# Sheet1.net
KiCad netlist of a schematic drawn in Altium Designer
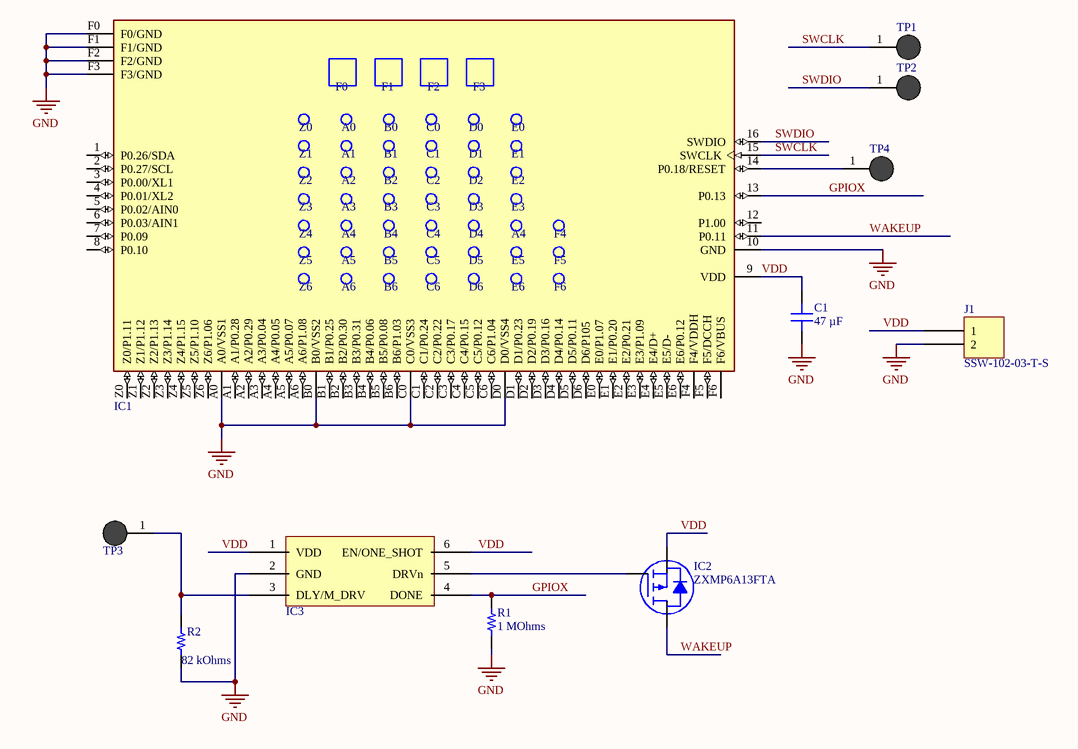
[diagram p0: Sheet1.SchDoc]

(export (version "E")
  (design (tool "Eeschema 10.0.6"))
  (components
    (comp (ref "C1")
      (value "47 µF")
      (footprint "CAP 1206_3216 - 0.8MM")
      (description "CAP CER 47UF 10V X5R 1206")
      (fields
        (field (name "PART NUMBER") "GRM31CR61A476ME15L")
        (field (name "MANUFACTURER") "Murata Electronics")
      )
      (libsource (lib "Celestial Altium Library - altium_library") (part "Capacitor"))
    )
    (comp (ref "IC1")
      (value "BT480F")
      (footprint "BT840F")
      (description "BLE 5 Module: Nordic nRF52840 SoC (Range 930 Meters)")
      (fields
        (field (name "MANUFACTURER") "Fanstel")
        (field (name "MANUFACTURER PART NUMBER") "BT840F")
        (field (name "DESIGNED BY") "Semih AŞÇI")
      )
      (libsource (lib "Integrated_Library1") (part "BT840F"))
    )
    (comp (ref "IC2")
      (value "ZXMP6A13FTA")
      (footprint "DIODES SOT-23-3")
      (description "MOSFET P-CH 60V 0.9A SOT23-3")
      (fields (field (name "MANUFACTURER") "Diodes Incorporated"))
      (libsource (lib "Celestial Altium Library - altium_library") (part "DIODES MOSFET P-CH SOT-23-3"))
    )
    (comp (ref "IC3")
      (value "TPL5111DDCT")
      (footprint "SOT-23-THN-6")
      (fields (field (name "MANUFACTURER") "Texas Instruments") (field (name "DESIGNED BY") "Semih AŞÇI"))
      (libsource (lib "Integrated_Library1") (part "TPL5111"))
    )
    (comp (ref "J1")
      (value "SSW-102-03-T-S")
      (footprint "SAMTEC SSW-102-03-T-S")
      (description "CONN RCPT 2POS 0.1 TIN PCB")
      (fields (field (name "MANUFACTURER") "Samtec Inc."))
      (libsource (lib "Celestial Altium Library - altium_library") (part "2 Pin"))
    )
    (comp (ref "R1")
      (value "1 MOhms")
      (footprint "RES 1206_3216")
      (description "RES SMD 1M OHM 1% 1/4W 1206")
      (fields (field (name "PART NUMBER") "RCA12061M00FKEA") (field (name "MANUFACTURER") "Vishay Dale"))
      (libsource (lib "Celestial Altium Library - altium_library") (part "Resistor"))
    )
    (comp (ref "R2")
      (value "82 kOhms")
      (footprint "RES 1206_3216")
      (description "RES 82K OHM 1% 1/2W 1206")
      (fields
        (field (name "PART NUMBER") "CRGP1206F82K")
        (field (name "MANUFACTURER") "TE Connectivity Passive Product")
      )
      (libsource (lib "Celestial Altium Library - altium_library") (part "Resistor"))
    )
    (comp (ref "TP1")
      (value "TEST PAD")
      (footprint "TEST_PAD")
      (libsource (lib "Integrated_Library1") (part "TEST PAD"))
    )
    (comp (ref "TP2")
      (value "TEST PAD")
      (footprint "TEST_PAD")
      (libsource (lib "Integrated_Library1") (part "TEST PAD"))
    )
    (comp (ref "TP3")
      (value "TEST PAD")
      (footprint "TEST_PAD")
      (libsource (lib "Integrated_Library1") (part "TEST PAD"))
    )
    (comp (ref "TP4")
      (value "TEST PAD")
      (footprint "TEST_PAD")
      (libsource (lib "Integrated_Library1") (part "TEST PAD"))
    )
  )
  (nets
    (net (code "1") (name "/GPIOX") (class "Default")
      (node (ref "IC1") (pin "13") (pinfunction "P0.13_13") (pintype "bidirectional"))
      (node (ref "IC3") (pin "4") (pinfunction "DONE_4") (pintype "passive"))
      (node (ref "R1") (pin "2") (pinfunction "2_2") (pintype "passive"))
    )
    (net (code "2") (name "/SWCLK") (class "Default")
      (node (ref "IC1") (pin "15") (pinfunction "SWCLK_15") (pintype "input"))
      (node (ref "TP1") (pin "1") (pinfunction "1_1") (pintype "passive"))
    )
    (net (code "3") (name "/SWDIO") (class "Default")
      (node (ref "IC1") (pin "16") (pinfunction "SWDIO_16") (pintype "bidirectional"))
      (node (ref "TP2") (pin "1") (pinfunction "1_1") (pintype "passive"))
    )
    (net (code "4") (name "/VDD") (class "Default")
      (node (ref "C1") (pin "2") (pinfunction "2_2") (pintype "passive"))
      (node (ref "IC1") (pin "9") (pinfunction "VDD_9") (pintype "power_in"))
      (node (ref "IC2") (pin "2") (pinfunction "S_2") (pintype "passive"))
      (node (ref "IC3") (pin "1") (pinfunction "VDD_1") (pintype "passive"))
      (node (ref "IC3") (pin "6") (pinfunction "EN/ONE_SHOT_6") (pintype "passive"))
      (node (ref "J1") (pin "1") (pinfunction "1_1") (pintype "passive"))
    )
    (net (code "5") (name "/WAKEUP") (class "Default")
      (node (ref "IC1") (pin "11") (pinfunction "P0.11_11") (pintype "bidirectional"))
      (node (ref "IC2") (pin "3") (pinfunction "D_3") (pintype "passive"))
    )
    (net (code "6") (name "GND") (class "Default")
      (node (ref "C1") (pin "1") (pinfunction "1_1") (pintype "passive"))
      (node (ref "IC1") (pin "10") (pinfunction "GND_10") (pintype "power_in"))
      (node (ref "IC1") (pin "A0") (pinfunction "A0/VSS1_A0") (pintype "power_in"))
      (node (ref "IC1") (pin "B0") (pinfunction "B0/VSS2_B0") (pintype "power_in"))
      (node (ref "IC1") (pin "C0") (pinfunction "C0/VSS3_C0") (pintype "power_in"))
      (node (ref "IC1") (pin "D0") (pinfunction "D0/VSS4_D0") (pintype "power_in"))
      (node (ref "IC1") (pin "F0") (pinfunction "F0/GND_F0") (pintype "power_in"))
      (node (ref "IC1") (pin "F1") (pinfunction "F1/GND_F1") (pintype "power_in"))
      (node (ref "IC1") (pin "F2") (pinfunction "F2/GND_F2") (pintype "power_in"))
      (node (ref "IC1") (pin "F3") (pinfunction "F3/GND_F3") (pintype "power_in"))
      (node (ref "IC3") (pin "2") (pinfunction "GND_2") (pintype "passive"))
      (node (ref "J1") (pin "2") (pinfunction "2_2") (pintype "passive"))
      (node (ref "R1") (pin "1") (pinfunction "1_1") (pintype "passive"))
      (node (ref "R2") (pin "1") (pinfunction "1_1") (pintype "passive"))
    )
    (net (code "7") (name "Net-(IC1-P0.18{slash}RESET)") (class "Default")
      (node (ref "IC1") (pin "14") (pinfunction "P0.18/RESET_14") (pintype "bidirectional"))
      (node (ref "TP4") (pin "1") (pinfunction "1_1") (pintype "passive"))
    )
    (net (code "8") (name "Net-(IC2-G)") (class "Default")
      (node (ref "IC2") (pin "1") (pinfunction "G_1") (pintype "passive"))
      (node (ref "IC3") (pin "5") (pinfunction "DRVn_5") (pintype "passive"))
    )
    (net (code "9") (name "Net-(IC3-DLY{slash}M_DRV)") (class "Default")
      (node (ref "IC3") (pin "3") (pinfunction "DLY/M_DRV_3") (pintype "passive"))
      (node (ref "R2") (pin "2") (pinfunction "2_2") (pintype "passive"))
      (node (ref "TP3") (pin "1") (pinfunction "1_1") (pintype "passive"))
    )
    (net (code "10") (name "unconnected-(IC1-A1{slash}P0.28-PadA1)") (class "Default")
      (node (ref "IC1") (pin "A1") (pinfunction "A1/P0.28_A1") (pintype "bidirectional"))
    )
    (net (code "11") (name "unconnected-(IC1-A2{slash}P0.29-PadA2)") (class "Default")
      (node (ref "IC1") (pin "A2") (pinfunction "A2/P0.29_A2") (pintype "bidirectional"))
    )
    (net (code "12") (name "unconnected-(IC1-A3{slash}P0.04-PadA3)") (class "Default")
      (node (ref "IC1") (pin "A3") (pinfunction "A3/P0.04_A3") (pintype "bidirectional"))
    )
    (net (code "13") (name "unconnected-(IC1-A4{slash}P0.05-PadA4)") (class "Default")
      (node (ref "IC1") (pin "A4") (pinfunction "A4/P0.05_A4") (pintype "bidirectional"))
    )
    (net (code "14") (name "unconnected-(IC1-A5{slash}P0.07-PadA5)") (class "Default")
      (node (ref "IC1") (pin "A5") (pinfunction "A5/P0.07_A5") (pintype "bidirectional"))
    )
    (net (code "15") (name "unconnected-(IC1-A6{slash}P1.08-PadA6)") (class "Default")
      (node (ref "IC1") (pin "A6") (pinfunction "A6/P1.08_A6") (pintype "bidirectional"))
    )
    (net (code "16") (name "unconnected-(IC1-B1{slash}P0.25-PadB1)") (class "Default")
      (node (ref "IC1") (pin "B1") (pinfunction "B1/P0.25_B1") (pintype "bidirectional"))
    )
    (net (code "17") (name "unconnected-(IC1-B2{slash}P0.30-PadB2)") (class "Default")
      (node (ref "IC1") (pin "B2") (pinfunction "B2/P0.30_B2") (pintype "bidirectional"))
    )
    (net (code "18") (name "unconnected-(IC1-B3{slash}P0.31-PadB3)") (class "Default")
      (node (ref "IC1") (pin "B3") (pinfunction "B3/P0.31_B3") (pintype "bidirectional"))
    )
    (net (code "19") (name "unconnected-(IC1-B4{slash}P0.06-PadB4)") (class "Default")
      (node (ref "IC1") (pin "B4") (pinfunction "B4/P0.06_B4") (pintype "bidirectional"))
    )
    (net (code "20") (name "unconnected-(IC1-B5{slash}P0.08-PadB5)") (class "Default")
      (node (ref "IC1") (pin "B5") (pinfunction "B5/P0.08_B5") (pintype "bidirectional"))
    )
    (net (code "21") (name "unconnected-(IC1-B6{slash}P1.03-PadB6)") (class "Default")
      (node (ref "IC1") (pin "B6") (pinfunction "B6/P1.03_B6") (pintype "bidirectional"))
    )
    (net (code "22") (name "unconnected-(IC1-C1{slash}P0.24-PadC1)") (class "Default")
      (node (ref "IC1") (pin "C1") (pinfunction "C1/P0.24_C1") (pintype "bidirectional"))
    )
    (net (code "23") (name "unconnected-(IC1-C2{slash}P0.22-PadC2)") (class "Default")
      (node (ref "IC1") (pin "C2") (pinfunction "C2/P0.22_C2") (pintype "bidirectional"))
    )
    (net (code "24") (name "unconnected-(IC1-C3{slash}P0.17-PadC3)") (class "Default")
      (node (ref "IC1") (pin "C3") (pinfunction "C3/P0.17_C3") (pintype "bidirectional"))
    )
    (net (code "25") (name "unconnected-(IC1-C4{slash}P0.15-PadC4)") (class "Default")
      (node (ref "IC1") (pin "C4") (pinfunction "C4/P0.15_C4") (pintype "bidirectional"))
    )
    (net (code "26") (name "unconnected-(IC1-C5{slash}P0.12-PadC5)") (class "Default")
      (node (ref "IC1") (pin "C5") (pinfunction "C5/P0.12_C5") (pintype "bidirectional"))
    )
    (net (code "27") (name "unconnected-(IC1-C6{slash}P1.04-PadC6)") (class "Default")
      (node (ref "IC1") (pin "C6") (pinfunction "C6/P1.04_C6") (pintype "bidirectional"))
    )
    (net (code "28") (name "unconnected-(IC1-D1{slash}P0.23-PadD1)") (class "Default")
      (node (ref "IC1") (pin "D1") (pinfunction "D1/P0.23_D1") (pintype "bidirectional"))
    )
    (net (code "29") (name "unconnected-(IC1-D2{slash}P0.19-PadD2)") (class "Default")
      (node (ref "IC1") (pin "D2") (pinfunction "D2/P0.19_D2") (pintype "bidirectional"))
    )
    (net (code "30") (name "unconnected-(IC1-D3{slash}P0.16-PadD3)") (class "Default")
      (node (ref "IC1") (pin "D3") (pinfunction "D3/P0.16_D3") (pintype "bidirectional"))
    )
    (net (code "31") (name "unconnected-(IC1-D4{slash}P0.14-PadD4)") (class "Default")
      (node (ref "IC1") (pin "D4") (pinfunction "D4/P0.14_D4") (pintype "bidirectional"))
    )
    (net (code "32") (name "unconnected-(IC1-D5{slash}P0.11-PadD5)") (class "Default")
      (node (ref "IC1") (pin "D5") (pinfunction "D5/P0.11_D5") (pintype "bidirectional"))
    )
    (net (code "33") (name "unconnected-(IC1-D6{slash}P105-PadD6)") (class "Default")
      (node (ref "IC1") (pin "D6") (pinfunction "D6/P105_D6") (pintype "bidirectional"))
    )
    (net (code "34") (name "unconnected-(IC1-E0{slash}P1.07-PadE0)") (class "Default")
      (node (ref "IC1") (pin "E0") (pinfunction "E0/P1.07_E0") (pintype "bidirectional"))
    )
    (net (code "35") (name "unconnected-(IC1-E1{slash}P0.20-PadE1)") (class "Default")
      (node (ref "IC1") (pin "E1") (pinfunction "E1/P0.20_E1") (pintype "bidirectional"))
    )
    (net (code "36") (name "unconnected-(IC1-E2{slash}P0.21-PadE2)") (class "Default")
      (node (ref "IC1") (pin "E2") (pinfunction "E2/P0.21_E2") (pintype "bidirectional"))
    )
    (net (code "37") (name "unconnected-(IC1-E3{slash}P1.09-PadE3)") (class "Default")
      (node (ref "IC1") (pin "E3") (pinfunction "E3/P1.09_E3") (pintype "bidirectional"))
    )
    (net (code "38") (name "unconnected-(IC1-E4{slash}D+-PadE4)") (class "Default")
      (node (ref "IC1") (pin "E4") (pinfunction "E4/D+_E4") (pintype "bidirectional"))
    )
    (net (code "39") (name "unconnected-(IC1-E5{slash}D--PadE5)") (class "Default")
      (node (ref "IC1") (pin "E5") (pinfunction "E5/D-_E5") (pintype "bidirectional"))
    )
    (net (code "40") (name "unconnected-(IC1-E6{slash}P0.12-PadE6)") (class "Default")
      (node (ref "IC1") (pin "E6") (pinfunction "E6/P0.12_E6") (pintype "bidirectional"))
    )
    (net (code "41") (name "unconnected-(IC1-F4{slash}VDDH-PadF4)") (class "Default")
      (node (ref "IC1") (pin "F4") (pinfunction "F4/VDDH_F4") (pintype "power_in"))
    )
    (net (code "42") (name "unconnected-(IC1-F5{slash}DCCH-PadF5)") (class "Default")
      (node (ref "IC1") (pin "F5") (pinfunction "F5/DCCH_F5") (pintype "bidirectional"))
    )
    (net (code "43") (name "unconnected-(IC1-F6{slash}VBUS-PadF6)") (class "Default")
      (node (ref "IC1") (pin "F6") (pinfunction "F6/VBUS_F6") (pintype "power_in"))
    )
    (net (code "44") (name "unconnected-(IC1-P0.00{slash}XL1-Pad3)") (class "Default")
      (node (ref "IC1") (pin "3") (pinfunction "P0.00/XL1_3") (pintype "bidirectional"))
    )
    (net (code "45") (name "unconnected-(IC1-P0.01{slash}XL2-Pad4)") (class "Default")
      (node (ref "IC1") (pin "4") (pinfunction "P0.01/XL2_4") (pintype "bidirectional"))
    )
    (net (code "46") (name "unconnected-(IC1-P0.02{slash}AIN0-Pad5)") (class "Default")
      (node (ref "IC1") (pin "5") (pinfunction "P0.02/AIN0_5") (pintype "bidirectional"))
    )
    (net (code "47") (name "unconnected-(IC1-P0.03{slash}AIN1-Pad6)") (class "Default")
      (node (ref "IC1") (pin "6") (pinfunction "P0.03/AIN1_6") (pintype "bidirectional"))
    )
    (net (code "48") (name "unconnected-(IC1-P0.09-Pad7)") (class "Default")
      (node (ref "IC1") (pin "7") (pinfunction "P0.09_7") (pintype "bidirectional"))
    )
    (net (code "49") (name "unconnected-(IC1-P0.10-Pad8)") (class "Default")
      (node (ref "IC1") (pin "8") (pinfunction "P0.10_8") (pintype "bidirectional"))
    )
    (net (code "50") (name "unconnected-(IC1-P0.26{slash}SDA-Pad1)") (class "Default")
      (node (ref "IC1") (pin "1") (pinfunction "P0.26/SDA_1") (pintype "bidirectional"))
    )
    (net (code "51") (name "unconnected-(IC1-P0.27{slash}SCL-Pad2)") (class "Default")
      (node (ref "IC1") (pin "2") (pinfunction "P0.27/SCL_2") (pintype "bidirectional"))
    )
    (net (code "52") (name "unconnected-(IC1-P1.00-Pad12)") (class "Default")
      (node (ref "IC1") (pin "12") (pinfunction "P1.00_12") (pintype "bidirectional"))
    )
    (net (code "53") (name "unconnected-(IC1-Z0{slash}P1.11-PadZ0)") (class "Default")
      (node (ref "IC1") (pin "Z0") (pinfunction "Z0/P1.11_Z0") (pintype "bidirectional"))
    )
    (net (code "54") (name "unconnected-(IC1-Z1{slash}P1.12-PadZ1)") (class "Default")
      (node (ref "IC1") (pin "Z1") (pinfunction "Z1/P1.12_Z1") (pintype "bidirectional"))
    )
    (net (code "55") (name "unconnected-(IC1-Z2{slash}P1.13-PadZ2)") (class "Default")
      (node (ref "IC1") (pin "Z2") (pinfunction "Z2/P1.13_Z2") (pintype "bidirectional"))
    )
    (net (code "56") (name "unconnected-(IC1-Z3{slash}P1.14-PadZ3)") (class "Default")
      (node (ref "IC1") (pin "Z3") (pinfunction "Z3/P1.14_Z3") (pintype "bidirectional"))
    )
    (net (code "57") (name "unconnected-(IC1-Z4{slash}P1.15-PadZ4)") (class "Default")
      (node (ref "IC1") (pin "Z4") (pinfunction "Z4/P1.15_Z4") (pintype "bidirectional"))
    )
    (net (code "58") (name "unconnected-(IC1-Z5{slash}P1.10-PadZ5)") (class "Default")
      (node (ref "IC1") (pin "Z5") (pinfunction "Z5/P1.10_Z5") (pintype "bidirectional"))
    )
    (net (code "59") (name "unconnected-(IC1-Z6{slash}P1.06-PadZ6)") (class "Default")
      (node (ref "IC1") (pin "Z6") (pinfunction "Z6/P1.06_Z6") (pintype "bidirectional"))
    )
  )
)
